# npm1300_qeaa_config1.net
KiCad netlist of a schematic drawn in Altium Designer
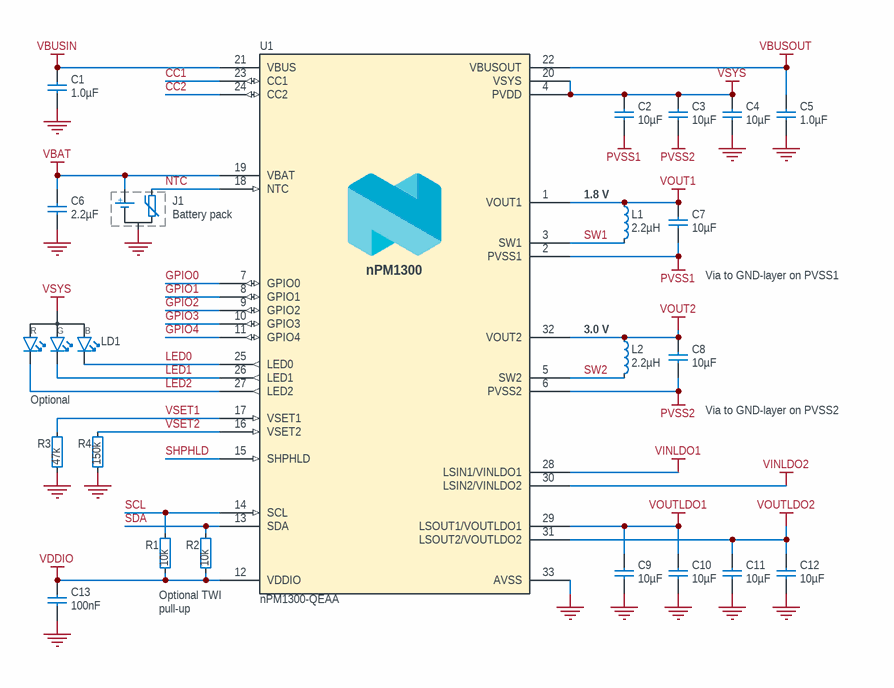
[diagram p0: npm1300_qeaa_config1.SchDoc]

(export (version "E")
  (design (tool "Eeschema 10.0.6"))
  (components
    (comp (ref "C1")
      (value "1.0µF")
      (footprint "CAPC1608X06L")
      (description "Capacitor, Ceramic, 1.0µF 10V X5R 0603,±10%")
      (fields
        (field (name "PART NUMBER") "C0603-1µ0-10V-X5R")
        (field (name "MANUFACTURER") "N.A.")
        (field (name "AUTHOR") "getr")
      )
      (libsource (lib "AltiumLib") (part "CAP"))
    )
    (comp (ref "C2")
      (value "10µF")
      (footprint "CAPC1608X06L")
      (description "Capacitor, X5R, ±20%")
      (fields
        (field (name "PART NUMBER") "C0603-10µ")
        (field (name "MANUFACTURER") "N.A.")
        (field (name "AUTHOR") "rsk")
      )
      (libsource (lib "AltiumLib") (part "CAP"))
    )
    (comp (ref "C3")
      (value "10µF")
      (footprint "CAPC1608X06L")
      (description "Capacitor, X5R, ±20%")
      (fields
        (field (name "PART NUMBER") "C0603-10µ")
        (field (name "MANUFACTURER") "N.A.")
        (field (name "AUTHOR") "rsk")
      )
      (libsource (lib "AltiumLib") (part "CAP"))
    )
    (comp (ref "C4")
      (value "10µF")
      (footprint "CAPC1608X06L")
      (description "Capacitor, X5R, ±20%")
      (fields
        (field (name "PART NUMBER") "C0603-10µ")
        (field (name "MANUFACTURER") "N.A.")
        (field (name "AUTHOR") "rsk")
      )
      (libsource (lib "AltiumLib") (part "CAP"))
    )
    (comp (ref "C5")
      (value "1.0µF")
      (footprint "CAPC1608X06L")
      (description "Capacitor, Ceramic, 1.0µF 10V X5R 0603,±10%")
      (fields
        (field (name "PART NUMBER") "C0603-1µ0-10V-X5R")
        (field (name "MANUFACTURER") "N.A.")
        (field (name "AUTHOR") "getr")
      )
      (libsource (lib "AltiumLib") (part "CAP"))
    )
    (comp (ref "C6")
      (value "2.2µF")
      (footprint "CAPC1608X06L")
      (description "Capacitor, Ceramic, X7R, ±10%, 16V")
      (fields
        (field (name "PART NUMBER") "C0603-2.2µ-16V-X7R")
        (field (name "MANUFACTURER") "Taiyo Yuden")
        (field (name "AUTHOR") "rsk")
      )
      (libsource (lib "AltiumLib") (part "CAP"))
    )
    (comp (ref "C7")
      (value "10µF")
      (footprint "CAPC1608X06L")
      (description "Capacitor, X5R, ±20%")
      (fields
        (field (name "PART NUMBER") "C0603-10µ")
        (field (name "MANUFACTURER") "N.A.")
        (field (name "AUTHOR") "rsk")
      )
      (libsource (lib "AltiumLib") (part "CAP"))
    )
    (comp (ref "C8")
      (value "10µF")
      (footprint "CAPC1608X06L")
      (description "Capacitor, X5R, ±20%")
      (fields
        (field (name "PART NUMBER") "C0603-10µ")
        (field (name "MANUFACTURER") "N.A.")
        (field (name "AUTHOR") "rsk")
      )
      (libsource (lib "AltiumLib") (part "CAP"))
    )
    (comp (ref "C9")
      (value "10µF")
      (footprint "CAPC1608X06L")
      (description "Capacitor, X5R, ±20%")
      (fields
        (field (name "PART NUMBER") "C0603-10µ")
        (field (name "MANUFACTURER") "N.A.")
        (field (name "AUTHOR") "rsk")
      )
      (libsource (lib "AltiumLib") (part "CAP"))
    )
    (comp (ref "C10")
      (value "10µF")
      (footprint "CAPC1608X06L")
      (description "Capacitor, X5R, ±20%")
      (fields
        (field (name "PART NUMBER") "C0603-10µ")
        (field (name "MANUFACTURER") "N.A.")
        (field (name "AUTHOR") "rsk")
      )
      (libsource (lib "AltiumLib") (part "CAP"))
    )
    (comp (ref "C11")
      (value "10µF")
      (footprint "CAPC1608X06L")
      (description "Capacitor, X5R, ±20%")
      (fields
        (field (name "PART NUMBER") "C0603-10µ")
        (field (name "MANUFACTURER") "N.A.")
        (field (name "AUTHOR") "rsk")
      )
      (libsource (lib "AltiumLib") (part "CAP"))
    )
    (comp (ref "C12")
      (value "10µF")
      (footprint "CAPC1608X06L")
      (description "Capacitor, X5R, ±20%")
      (fields
        (field (name "PART NUMBER") "C0603-10µ")
        (field (name "MANUFACTURER") "N.A.")
        (field (name "AUTHOR") "rsk")
      )
      (libsource (lib "AltiumLib") (part "CAP"))
    )
    (comp (ref "C13")
      (value "100nF")
      (footprint "CAPC0603X03L_C")
      (description "Capacitor, X5R, ±10%")
      (fields
        (field (name "PART NUMBER") "C0201-100n")
        (field (name "MANUFACTURER") "N.A.")
        (field (name "AUTHOR") "rsk")
      )
      (libsource (lib "AltiumLib") (part "CAP"))
    )
    (comp (ref "J1")
      (value "Battery pack")
      (footprint "TP_3x1mm_TH")
      (description "Battery pack with NTC")
      (fields
        (field (name "PART NUMBER") "Battery_w/NTC_TP")
        (field (name "MANUFACTURER") "N.A.")
        (field (name "AUTHOR") "rsk")
      )
      (libsource (lib "AltiumLib") (part "Battery_pack_NTC"))
    )
    (comp (ref "L1")
      (value "2.2µH")
      (footprint "INDC2016X10N")
      (description "Inductor, Irms=2.5A, Isat=2.9A, ±20%, DCR=73mΩ")
      (fields
        (field (name "PART NUMBER") "L0806-2µ2-2500mA-73mOhm-CIGT201610EH2R2MNE")
        (field (name "MANUFACTURER") "Samsung Electro-Mechanics")
        (field (name "AUTHOR") "rsk")
      )
      (libsource (lib "AltiumLib") (part "IND"))
    )
    (comp (ref "L2")
      (value "2.2µH")
      (footprint "INDC2016X10N")
      (description "Inductor, Irms=2.5A, Isat=2.9A, ±20%, DCR=73mΩ")
      (fields
        (field (name "PART NUMBER") "L0806-2µ2-2500mA-73mOhm-CIGT201610EH2R2MNE")
        (field (name "MANUFACTURER") "Samsung Electro-Mechanics")
        (field (name "AUTHOR") "rsk")
      )
      (libsource (lib "AltiumLib") (part "IND"))
    )
    (comp (ref "LD1")
      (value "LED RGB")
      (footprint "LED_RGB_0603")
      (description "RGB LED 1.60 mm x 0.80 mm SMD")
      (fields
        (field (name "PART NUMBER") "APHF1608LSEEQBDZGKC")
        (field (name "MANUFACTURER") "Kingbright Company LLC")
        (field (name "AUTHOR") "rsk")
      )
      (libsource (lib "AltiumLib") (part "D{colon}LED_RGB"))
    )
    (comp (ref "R1")
      (value "10k")
      (footprint "RESC0603X03L_C")
      (description "Resistor, ±1%, 0.05W")
      (fields
        (field (name "PART NUMBER") "R0201-10k")
        (field (name "MANUFACTURER") "N.A.")
        (field (name "AUTHOR") "rsk")
      )
      (libsource (lib "AltiumLib") (part "RES"))
    )
    (comp (ref "R2")
      (value "10k")
      (footprint "RESC0603X03L_C")
      (description "Resistor, ±1%, 0.05W")
      (fields
        (field (name "PART NUMBER") "R0201-10k")
        (field (name "MANUFACTURER") "N.A.")
        (field (name "AUTHOR") "rsk")
      )
      (libsource (lib "AltiumLib") (part "RES"))
    )
    (comp (ref "R3")
      (value "47k")
      (footprint "RESC0603X03L_C")
      (description "Resistor, ±1%, 0.05W")
      (fields
        (field (name "PART NUMBER") "R0201-47k")
        (field (name "MANUFACTURER") "N.A.")
        (field (name "AUTHOR") "rsk")
      )
      (libsource (lib "AltiumLib") (part "RES"))
    )
    (comp (ref "R4")
      (value "150k")
      (footprint "RESC0603X03L_C")
      (description "Resistor, ±1%, 0.05W")
      (fields
        (field (name "PART NUMBER") "R0201-150k")
        (field (name "MANUFACTURER") "N.A.")
        (field (name "AUTHOR") "rsk")
      )
      (libsource (lib "AltiumLib") (part "RES"))
    )
    (comp (ref "U1")
      (value "nPM1300-QEAA")
      (footprint "Nordic_QFN50P500X500X90-33N")
      (fields (field (name "MANUFACTURER") "Nordic Semiconductor") (field (name "AUTHOR") "eisk"))
      (libsource (lib "AltiumLib") (part "nPM1300_QEAA"))
    )
  )
  (nets
    (net (code "1") (name "/CC1") (class "Default")
      (node (ref "U1") (pin "23") (pinfunction "CC1_23") (pintype "bidirectional"))
    )
    (net (code "2") (name "/CC2") (class "Default")
      (node (ref "U1") (pin "24") (pinfunction "CC2_24") (pintype "bidirectional"))
    )
    (net (code "3") (name "/GPIO0") (class "Default")
      (node (ref "U1") (pin "7") (pinfunction "GPIO0_7") (pintype "bidirectional"))
    )
    (net (code "4") (name "/GPIO1") (class "Default")
      (node (ref "U1") (pin "8") (pinfunction "GPIO1_8") (pintype "bidirectional"))
    )
    (net (code "5") (name "/GPIO2") (class "Default")
      (node (ref "U1") (pin "9") (pinfunction "GPIO2_9") (pintype "bidirectional"))
    )
    (net (code "6") (name "/GPIO3") (class "Default")
      (node (ref "U1") (pin "10") (pinfunction "GPIO3_10") (pintype "bidirectional"))
    )
    (net (code "7") (name "/GPIO4") (class "Default")
      (node (ref "U1") (pin "11") (pinfunction "GPIO4_11") (pintype "bidirectional"))
    )
    (net (code "8") (name "/LED0") (class "Default")
      (node (ref "LD1") (pin "3") (pinfunction "C_BLUE_3") (pintype "passive"))
      (node (ref "U1") (pin "25") (pinfunction "LED0_25") (pintype "output"))
    )
    (net (code "9") (name "/LED1") (class "Default")
      (node (ref "LD1") (pin "2") (pinfunction "C_GREEN_2") (pintype "passive"))
      (node (ref "U1") (pin "26") (pinfunction "LED1_26") (pintype "output"))
    )
    (net (code "10") (name "/LED2") (class "Default")
      (node (ref "LD1") (pin "1") (pinfunction "C_RED_1") (pintype "passive"))
      (node (ref "U1") (pin "27") (pinfunction "LED2_27") (pintype "output"))
    )
    (net (code "11") (name "/NTC") (class "Default")
      (node (ref "J1") (pin "2") (pinfunction "NTC_2") (pintype "passive"))
      (node (ref "U1") (pin "18") (pinfunction "NTC_18") (pintype "input"))
    )
    (net (code "12") (name "/SCL") (class "Default")
      (node (ref "R1") (pin "1") (pinfunction "1_1") (pintype "passive"))
      (node (ref "U1") (pin "14") (pinfunction "SCL_14") (pintype "input"))
    )
    (net (code "13") (name "/SDA") (class "Default")
      (node (ref "R2") (pin "1") (pinfunction "1_1") (pintype "passive"))
      (node (ref "U1") (pin "13") (pinfunction "SDA_13") (pintype "open_collector"))
    )
    (net (code "14") (name "/SHPHLD") (class "Default")
      (node (ref "U1") (pin "15") (pinfunction "SHPHLD_15") (pintype "input"))
    )
    (net (code "15") (name "/SW1") (class "Default")
      (node (ref "L1") (pin "2") (pinfunction "2_2") (pintype "passive"))
      (node (ref "U1") (pin "3") (pinfunction "SW1_3") (pintype "power_in"))
    )
    (net (code "16") (name "/SW2") (class "Default")
      (node (ref "L2") (pin "2") (pinfunction "2_2") (pintype "passive"))
      (node (ref "U1") (pin "5") (pinfunction "SW2_5") (pintype "power_in"))
    )
    (net (code "17") (name "/VSET1") (class "Default")
      (node (ref "R3") (pin "1") (pinfunction "1_1") (pintype "passive"))
      (node (ref "U1") (pin "17") (pinfunction "VSET1_17") (pintype "input"))
    )
    (net (code "18") (name "/VSET2") (class "Default")
      (node (ref "R4") (pin "1") (pinfunction "1_1") (pintype "passive"))
      (node (ref "U1") (pin "16") (pinfunction "VSET2_16") (pintype "input"))
    )
    (net (code "19") (name "GND") (class "Default")
      (node (ref "C1") (pin "1") (pinfunction "1_1") (pintype "passive"))
      (node (ref "C10") (pin "1") (pinfunction "1_1") (pintype "passive"))
      (node (ref "C11") (pin "1") (pinfunction "1_1") (pintype "passive"))
      (node (ref "C12") (pin "1") (pinfunction "1_1") (pintype "passive"))
      (node (ref "C13") (pin "2") (pinfunction "2_2") (pintype "passive"))
      (node (ref "C4") (pin "1") (pinfunction "1_1") (pintype "passive"))
      (node (ref "C5") (pin "1") (pinfunction "1_1") (pintype "passive"))
      (node (ref "C6") (pin "1") (pinfunction "1_1") (pintype "passive"))
      (node (ref "C9") (pin "1") (pinfunction "1_1") (pintype "passive"))
      (node (ref "J1") (pin "1") (pinfunction "GND_1") (pintype "passive"))
      (node (ref "R3") (pin "2") (pinfunction "2_2") (pintype "passive"))
      (node (ref "R4") (pin "2") (pinfunction "2_2") (pintype "passive"))
      (node (ref "U1") (pin "33") (pinfunction "AVSS_33") (pintype "power_in"))
    )
    (net (code "20") (name "PVSS1") (class "Default")
      (node (ref "C2") (pin "1") (pinfunction "1_1") (pintype "passive"))
      (node (ref "C7") (pin "1") (pinfunction "1_1") (pintype "passive"))
      (node (ref "U1") (pin "2") (pinfunction "PVSS1_2") (pintype "power_in"))
    )
    (net (code "21") (name "PVSS2") (class "Default")
      (node (ref "C3") (pin "1") (pinfunction "1_1") (pintype "passive"))
      (node (ref "C8") (pin "1") (pinfunction "1_1") (pintype "passive"))
      (node (ref "U1") (pin "6") (pinfunction "PVSS2_6") (pintype "power_in"))
    )
    (net (code "22") (name "VBAT") (class "Default")
      (node (ref "C6") (pin "2") (pinfunction "2_2") (pintype "passive"))
      (node (ref "J1") (pin "3") (pinfunction "V+_3") (pintype "passive"))
      (node (ref "U1") (pin "19") (pinfunction "VBAT_19") (pintype "passive"))
    )
    (net (code "23") (name "VBUSIN") (class "Default")
      (node (ref "C1") (pin "2") (pinfunction "2_2") (pintype "passive"))
      (node (ref "U1") (pin "21") (pinfunction "VBUS_21") (pintype "power_in"))
    )
    (net (code "24") (name "VBUSOUT") (class "Default")
      (node (ref "C5") (pin "2") (pinfunction "2_2") (pintype "passive"))
      (node (ref "U1") (pin "22") (pinfunction "VBUSOUT_22") (pintype "power_in"))
    )
    (net (code "25") (name "VDDIO") (class "Default")
      (node (ref "C13") (pin "1") (pinfunction "1_1") (pintype "passive"))
      (node (ref "R1") (pin "2") (pinfunction "2_2") (pintype "passive"))
      (node (ref "R2") (pin "2") (pinfunction "2_2") (pintype "passive"))
      (node (ref "U1") (pin "12") (pinfunction "VDDIO_12") (pintype "power_in"))
    )
    (net (code "26") (name "VINLDO1") (class "Default")
      (node (ref "U1") (pin "28") (pinfunction "LSIN1/VINLDO1_28") (pintype "power_in"))
    )
    (net (code "27") (name "VINLDO2") (class "Default")
      (node (ref "U1") (pin "30") (pinfunction "LSIN2/VINLDO2_30") (pintype "power_in"))
    )
    (net (code "28") (name "VOUT1") (class "Default")
      (node (ref "C7") (pin "2") (pinfunction "2_2") (pintype "passive"))
      (node (ref "L1") (pin "1") (pinfunction "1_1") (pintype "passive"))
      (node (ref "U1") (pin "1") (pinfunction "VOUT1_1") (pintype "power_in"))
    )
    (net (code "29") (name "VOUT2") (class "Default")
      (node (ref "C8") (pin "2") (pinfunction "2_2") (pintype "passive"))
      (node (ref "L2") (pin "1") (pinfunction "1_1") (pintype "passive"))
      (node (ref "U1") (pin "32") (pinfunction "VOUT2_32") (pintype "power_in"))
    )
    (net (code "30") (name "VOUTLDO1") (class "Default")
      (node (ref "C10") (pin "2") (pinfunction "2_2") (pintype "passive"))
      (node (ref "C9") (pin "2") (pinfunction "2_2") (pintype "passive"))
      (node (ref "U1") (pin "29") (pinfunction "LSOUT1/VOUTLDO1_29") (pintype "power_in"))
    )
    (net (code "31") (name "VOUTLDO2") (class "Default")
      (node (ref "C11") (pin "2") (pinfunction "2_2") (pintype "passive"))
      (node (ref "C12") (pin "2") (pinfunction "2_2") (pintype "passive"))
      (node (ref "U1") (pin "31") (pinfunction "LSOUT2/VOUTLDO2_31") (pintype "power_in"))
    )
    (net (code "32") (name "VSYS") (class "Default")
      (node (ref "C2") (pin "2") (pinfunction "2_2") (pintype "passive"))
      (node (ref "C3") (pin "2") (pinfunction "2_2") (pintype "passive"))
      (node (ref "C4") (pin "2") (pinfunction "2_2") (pintype "passive"))
      (node (ref "LD1") (pin "4") (pinfunction "A_4") (pintype "passive"))
      (node (ref "U1") (pin "20") (pinfunction "VSYS_20") (pintype "power_in"))
      (node (ref "U1") (pin "4") (pinfunction "PVDD_4") (pintype "power_in"))
    )
  )
)
